# Chroma-Color_Rails.net
KiCad netlist of a schematic drawn in EAGLE
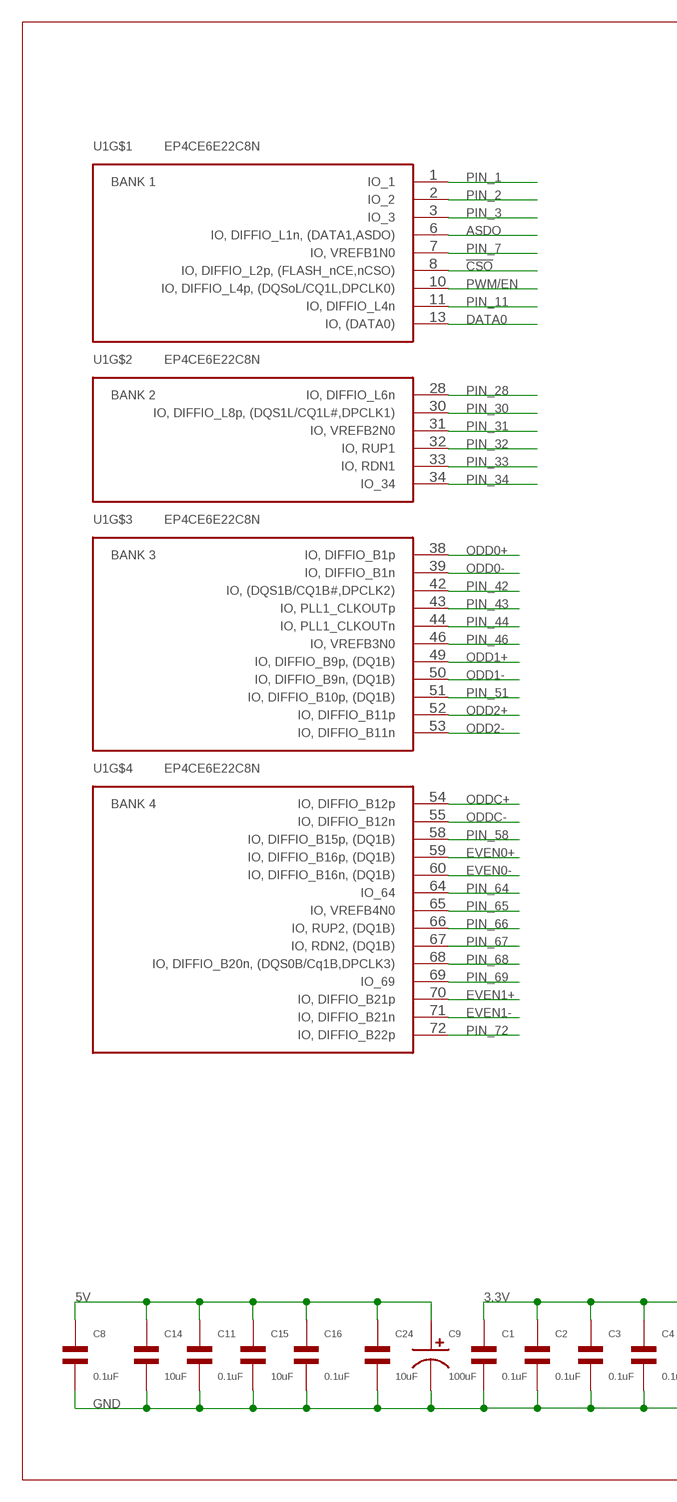
[diagram p0: schematic, sheet 1, part 1 of 2]
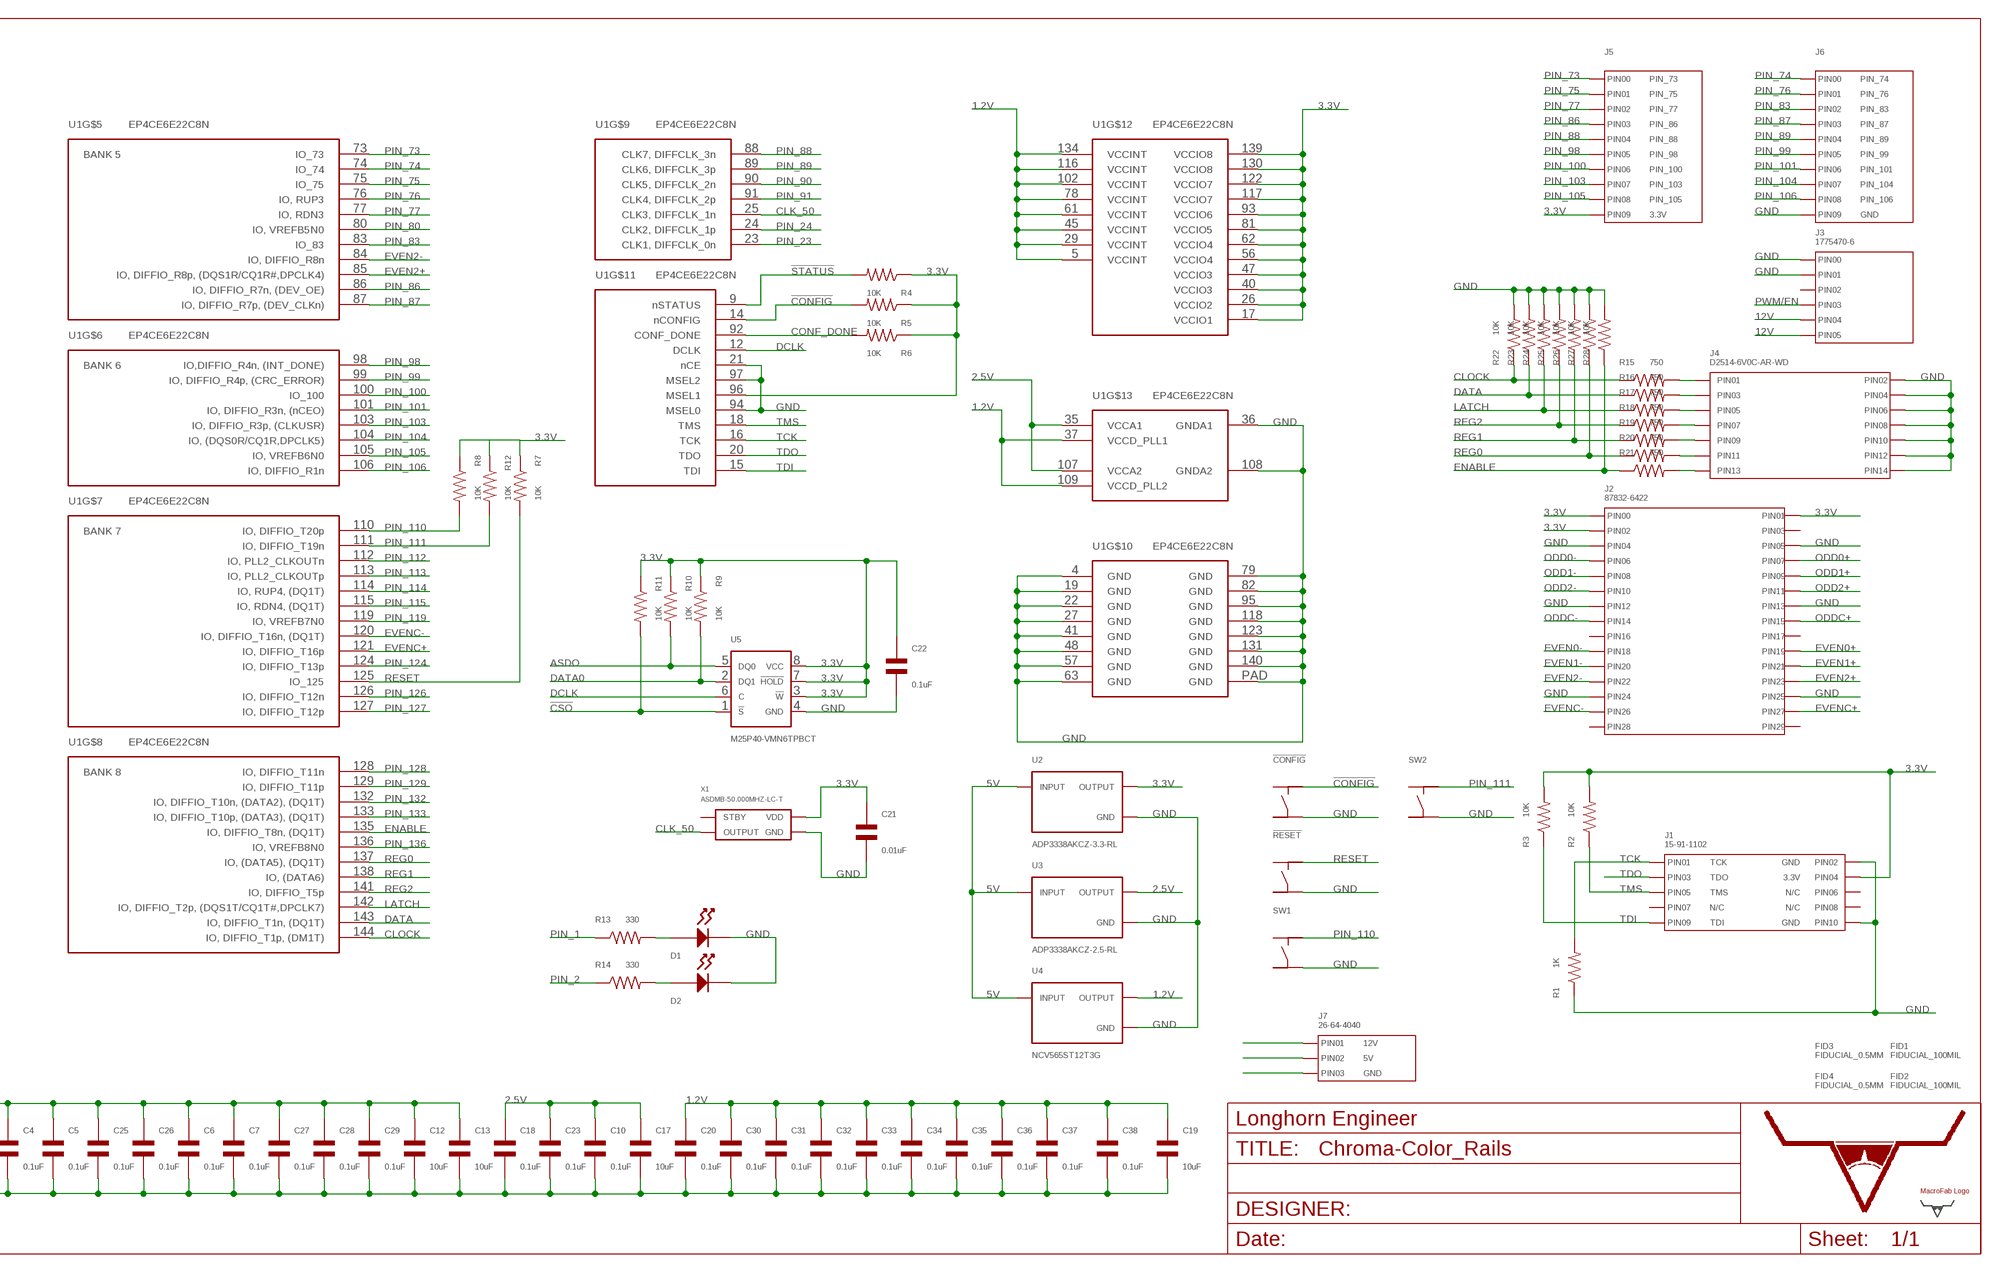
[diagram p1: schematic, sheet 1, part 2 of 2]

(export (version "E")
  (design (tool "Eeschema 10.0.6"))
  (components
    (comp (ref "!CONFIG")
      (value "TACT_4.2MM")
      (footprint "eagle-import:TACT4.2MM")
      (libsource (lib "eagle-import") (part "TACT_4.2MM"))
    )
    (comp (ref "!RESET")
      (value "TACT_4.2MM")
      (footprint "eagle-import:TACT4.2MM")
      (libsource (lib "eagle-import") (part "TACT_4.2MM"))
    )
    (comp (ref "C1")
      (value "0.1uF")
      (footprint "eagle-import:C0603")
      (libsource (lib "eagle-import") (part "CAPACITOR_NP_0603"))
    )
    (comp (ref "C2")
      (value "0.1uF")
      (footprint "eagle-import:C0603")
      (libsource (lib "eagle-import") (part "CAPACITOR_NP_0603"))
    )
    (comp (ref "C3")
      (value "0.1uF")
      (footprint "eagle-import:C0603")
      (libsource (lib "eagle-import") (part "CAPACITOR_NP_0603"))
    )
    (comp (ref "C4")
      (value "0.1uF")
      (footprint "eagle-import:C0603")
      (libsource (lib "eagle-import") (part "CAPACITOR_NP_0603"))
    )
    (comp (ref "C5")
      (value "0.1uF")
      (footprint "eagle-import:C0603")
      (libsource (lib "eagle-import") (part "CAPACITOR_NP_0603"))
    )
    (comp (ref "C6")
      (value "0.1uF")
      (footprint "eagle-import:C0603")
      (libsource (lib "eagle-import") (part "CAPACITOR_NP_0603"))
    )
    (comp (ref "C7")
      (value "0.1uF")
      (footprint "eagle-import:C0603")
      (libsource (lib "eagle-import") (part "CAPACITOR_NP_0603"))
    )
    (comp (ref "C8")
      (value "0.1uF")
      (footprint "eagle-import:C0603")
      (libsource (lib "eagle-import") (part "CAPACITOR_NP_0603"))
    )
    (comp (ref "C9")
      (value "100uF")
      (footprint "eagle-import:CP6.3MM")
      (libsource (lib "eagle-import") (part "CAPACITOR_P_6.3MM"))
    )
    (comp (ref "C10")
      (value "0.1uF")
      (footprint "eagle-import:C0603")
      (libsource (lib "eagle-import") (part "CAPACITOR_NP_0603"))
    )
    (comp (ref "C11")
      (value "0.1uF")
      (footprint "eagle-import:C0603")
      (libsource (lib "eagle-import") (part "CAPACITOR_NP_0603"))
    )
    (comp (ref "C12")
      (value "10uF")
      (footprint "eagle-import:C0603")
      (libsource (lib "eagle-import") (part "CAPACITOR_NP_0603"))
    )
    (comp (ref "C13")
      (value "10uF")
      (footprint "eagle-import:C0603")
      (libsource (lib "eagle-import") (part "CAPACITOR_NP_0603"))
    )
    (comp (ref "C14")
      (value "10uF")
      (footprint "eagle-import:C0603")
      (libsource (lib "eagle-import") (part "CAPACITOR_NP_0603"))
    )
    (comp (ref "C15")
      (value "10uF")
      (footprint "eagle-import:C0603")
      (libsource (lib "eagle-import") (part "CAPACITOR_NP_0603"))
    )
    (comp (ref "C16")
      (value "0.1uF")
      (footprint "eagle-import:C0603")
      (libsource (lib "eagle-import") (part "CAPACITOR_NP_0603"))
    )
    (comp (ref "C17")
      (value "10uF")
      (footprint "eagle-import:C0603")
      (libsource (lib "eagle-import") (part "CAPACITOR_NP_0603"))
    )
    (comp (ref "C18")
      (value "0.1uF")
      (footprint "eagle-import:C0603")
      (libsource (lib "eagle-import") (part "CAPACITOR_NP_0603"))
    )
    (comp (ref "C19")
      (value "10uF")
      (footprint "eagle-import:C0603")
      (libsource (lib "eagle-import") (part "CAPACITOR_NP_0603"))
    )
    (comp (ref "C20")
      (value "0.1uF")
      (footprint "eagle-import:C0603")
      (libsource (lib "eagle-import") (part "CAPACITOR_NP_0603"))
    )
    (comp (ref "C21")
      (value "0.01uF")
      (footprint "eagle-import:C0603")
      (libsource (lib "eagle-import") (part "CAPACITOR_NP_0603"))
    )
    (comp (ref "C22")
      (value "0.1uF")
      (footprint "eagle-import:C0603")
      (libsource (lib "eagle-import") (part "CAPACITOR_NP_0603"))
    )
    (comp (ref "C23")
      (value "0.1uF")
      (footprint "eagle-import:C0603")
      (libsource (lib "eagle-import") (part "CAPACITOR_NP_0603"))
    )
    (comp (ref "C24")
      (value "10uF")
      (footprint "eagle-import:C0603")
      (libsource (lib "eagle-import") (part "CAPACITOR_NP_0603"))
    )
    (comp (ref "C25")
      (value "0.1uF")
      (footprint "eagle-import:C0603")
      (libsource (lib "eagle-import") (part "CAPACITOR_NP_0603"))
    )
    (comp (ref "C26")
      (value "0.1uF")
      (footprint "eagle-import:C0603")
      (libsource (lib "eagle-import") (part "CAPACITOR_NP_0603"))
    )
    (comp (ref "C27")
      (value "0.1uF")
      (footprint "eagle-import:C0603")
      (libsource (lib "eagle-import") (part "CAPACITOR_NP_0603"))
    )
    (comp (ref "C28")
      (value "0.1uF")
      (footprint "eagle-import:C0603")
      (libsource (lib "eagle-import") (part "CAPACITOR_NP_0603"))
    )
    (comp (ref "C29")
      (value "0.1uF")
      (footprint "eagle-import:C0603")
      (libsource (lib "eagle-import") (part "CAPACITOR_NP_0603"))
    )
    (comp (ref "C30")
      (value "0.1uF")
      (footprint "eagle-import:C0603")
      (libsource (lib "eagle-import") (part "CAPACITOR_NP_0603"))
    )
    (comp (ref "C31")
      (value "0.1uF")
      (footprint "eagle-import:C0603")
      (libsource (lib "eagle-import") (part "CAPACITOR_NP_0603"))
    )
    (comp (ref "C32")
      (value "0.1uF")
      (footprint "eagle-import:C0603")
      (libsource (lib "eagle-import") (part "CAPACITOR_NP_0603"))
    )
    (comp (ref "C33")
      (value "0.1uF")
      (footprint "eagle-import:C0603")
      (libsource (lib "eagle-import") (part "CAPACITOR_NP_0603"))
    )
    (comp (ref "C34")
      (value "0.1uF")
      (footprint "eagle-import:C0603")
      (libsource (lib "eagle-import") (part "CAPACITOR_NP_0603"))
    )
    (comp (ref "C35")
      (value "0.1uF")
      (footprint "eagle-import:C0603")
      (libsource (lib "eagle-import") (part "CAPACITOR_NP_0603"))
    )
    (comp (ref "C36")
      (value "0.1uF")
      (footprint "eagle-import:C0603")
      (libsource (lib "eagle-import") (part "CAPACITOR_NP_0603"))
    )
    (comp (ref "C37")
      (value "0.1uF")
      (footprint "eagle-import:C0603")
      (libsource (lib "eagle-import") (part "CAPACITOR_NP_0603"))
    )
    (comp (ref "C38")
      (value "0.1uF")
      (footprint "eagle-import:C0603")
      (libsource (lib "eagle-import") (part "CAPACITOR_NP_0603"))
    )
    (comp (ref "D1")
      (value "LED_SINGLE_0805")
      (footprint "eagle-import:LED0805")
      (libsource (lib "eagle-import") (part "LED_SINGLE_0805"))
    )
    (comp (ref "D2")
      (value "LED_SINGLE_0805")
      (footprint "eagle-import:LED0805")
      (libsource (lib "eagle-import") (part "LED_SINGLE_0805"))
    )
    (comp (ref "FID1")
      (value "FIDUCIAL_100MIL")
      (footprint "eagle-import:FIDUCIAL_100MIL")
      (libsource (lib "eagle-import") (part "FIDUCIAL_100MIL"))
    )
    (comp (ref "FID2")
      (value "FIDUCIAL_100MIL")
      (footprint "eagle-import:FIDUCIAL_100MIL")
      (libsource (lib "eagle-import") (part "FIDUCIAL_100MIL"))
    )
    (comp (ref "FID3")
      (value "FIDUCIAL_0.5MM")
      (footprint "eagle-import:FIDUCIAL_0.5MM")
      (libsource (lib "eagle-import") (part "FIDUCIAL_0.5MM"))
    )
    (comp (ref "FID4")
      (value "FIDUCIAL_0.5MM")
      (footprint "eagle-import:FIDUCIAL_0.5MM")
      (libsource (lib "eagle-import") (part "FIDUCIAL_0.5MM"))
    )
    (comp (ref "J1")
      (value "15-91-1102")
      (footprint "eagle-import:15-91-1102")
      (fields
        (field (name "LABEL01") "TCK")
        (field (name "LABEL02") "GND")
        (field (name "LABEL03") "TDO")
        (field (name "LABEL04") "3.3V")
        (field (name "LABEL05") "TMS")
        (field (name "LABEL06") "N/C")
        (field (name "LABEL07") "N/C")
        (field (name "LABEL08") "N/C")
        (field (name "LABEL09") "TDI")
        (field (name "LABEL10") "GND")
      )
      (libsource (lib "eagle-import") (part "15-91-1102"))
    )
    (comp (ref "J2")
      (value "87832-6422")
      (footprint "eagle-import:87832-6422")
      (libsource (lib "eagle-import") (part "87832-6422"))
    )
    (comp (ref "J3")
      (value "1775470-6")
      (footprint "eagle-import:1775470-6")
      (libsource (lib "eagle-import") (part "1775470-6"))
    )
    (comp (ref "J4")
      (value "D2514-6V0C-AR-WD")
      (footprint "eagle-import:D2514-6V0C-AR-WD")
      (libsource (lib "eagle-import") (part "SMT_02X07D2514-6V0C-AR-WD"))
    )
    (comp (ref "J5")
      (value "HEADER_01X10_PTH_2.54MM")
      (footprint "eagle-import:PTH_2.54MM_01X10")
      (fields
        (field (name "LABEL00") "PIN_73")
        (field (name "LABEL01") "PIN_75")
        (field (name "LABEL02") "PIN_77")
        (field (name "LABEL03") "PIN_86")
        (field (name "LABEL04") "PIN_88")
        (field (name "LABEL05") "PIN_98")
        (field (name "LABEL06") "PIN_100")
        (field (name "LABEL07") "PIN_103")
        (field (name "LABEL08") "PIN_105")
        (field (name "LABEL09") "3.3V")
      )
      (libsource (lib "eagle-import") (part "HEADER_01X10_PTH_2.54MM"))
    )
    (comp (ref "J6")
      (value "HEADER_01X10_PTH_2.54MM")
      (footprint "eagle-import:PTH_2.54MM_01X10")
      (fields
        (field (name "LABEL00") "PIN_74")
        (field (name "LABEL01") "PIN_76")
        (field (name "LABEL02") "PIN_83")
        (field (name "LABEL03") "PIN_87")
        (field (name "LABEL04") "PIN_89")
        (field (name "LABEL05") "PIN_99")
        (field (name "LABEL06") "PIN_101")
        (field (name "LABEL07") "PIN_104")
        (field (name "LABEL08") "PIN_106")
        (field (name "LABEL09") "GND")
      )
      (libsource (lib "eagle-import") (part "HEADER_01X10_PTH_2.54MM"))
    )
    (comp (ref "J7")
      (value "26-64-4040")
      (footprint "eagle-import:MOLEX_KK_4_P1")
      (fields (field (name "LABEL01") "12V") (field (name "LABEL02") "5V") (field (name "LABEL03") "GND"))
      (libsource (lib "eagle-import") (part "HEADER_01X03MOLEX_KK_4_P1"))
    )
    (comp (ref "R1")
      (value "1K")
      (footprint "eagle-import:R0603")
      (libsource (lib "eagle-import") (part "RESISTOR_0603"))
    )
    (comp (ref "R2")
      (value "10K")
      (footprint "eagle-import:R0603")
      (libsource (lib "eagle-import") (part "RESISTOR_0603"))
    )
    (comp (ref "R3")
      (value "10K")
      (footprint "eagle-import:R0603")
      (libsource (lib "eagle-import") (part "RESISTOR_0603"))
    )
    (comp (ref "R4")
      (value "10K")
      (footprint "eagle-import:R0603")
      (libsource (lib "eagle-import") (part "RESISTOR_0603"))
    )
    (comp (ref "R5")
      (value "10K")
      (footprint "eagle-import:R0603")
      (libsource (lib "eagle-import") (part "RESISTOR_0603"))
    )
    (comp (ref "R6")
      (value "10K")
      (footprint "eagle-import:R0603")
      (libsource (lib "eagle-import") (part "RESISTOR_0603"))
    )
    (comp (ref "R7")
      (value "10K")
      (footprint "eagle-import:R0603")
      (libsource (lib "eagle-import") (part "RESISTOR_0603"))
    )
    (comp (ref "R8")
      (value "10K")
      (footprint "eagle-import:R0603")
      (libsource (lib "eagle-import") (part "RESISTOR_0603"))
    )
    (comp (ref "R9")
      (value "10K")
      (footprint "eagle-import:R0603")
      (libsource (lib "eagle-import") (part "RESISTOR_0603"))
    )
    (comp (ref "R10")
      (value "10K")
      (footprint "eagle-import:R0603")
      (libsource (lib "eagle-import") (part "RESISTOR_0603"))
    )
    (comp (ref "R11")
      (value "10K")
      (footprint "eagle-import:R0603")
      (libsource (lib "eagle-import") (part "RESISTOR_0603"))
    )
    (comp (ref "R12")
      (value "10K")
      (footprint "eagle-import:R0603")
      (libsource (lib "eagle-import") (part "RESISTOR_0603"))
    )
    (comp (ref "R13")
      (value "330")
      (footprint "eagle-import:R0603")
      (libsource (lib "eagle-import") (part "RESISTOR_0603"))
    )
    (comp (ref "R14")
      (value "330")
      (footprint "eagle-import:R0603")
      (libsource (lib "eagle-import") (part "RESISTOR_0603"))
    )
    (comp (ref "R15")
      (value "750")
      (footprint "eagle-import:R0603")
      (libsource (lib "eagle-import") (part "RESISTOR_0603"))
    )
    (comp (ref "R16")
      (value "750")
      (footprint "eagle-import:R0603")
      (libsource (lib "eagle-import") (part "RESISTOR_0603"))
    )
    (comp (ref "R17")
      (value "750")
      (footprint "eagle-import:R0603")
      (libsource (lib "eagle-import") (part "RESISTOR_0603"))
    )
    (comp (ref "R18")
      (value "750")
      (footprint "eagle-import:R0603")
      (libsource (lib "eagle-import") (part "RESISTOR_0603"))
    )
    (comp (ref "R19")
      (value "750")
      (footprint "eagle-import:R0603")
      (libsource (lib "eagle-import") (part "RESISTOR_0603"))
    )
    (comp (ref "R20")
      (value "750")
      (footprint "eagle-import:R0603")
      (libsource (lib "eagle-import") (part "RESISTOR_0603"))
    )
    (comp (ref "R21")
      (value "750")
      (footprint "eagle-import:R0603")
      (libsource (lib "eagle-import") (part "RESISTOR_0603"))
    )
    (comp (ref "R22")
      (value "10K")
      (footprint "eagle-import:R0603")
      (libsource (lib "eagle-import") (part "RESISTOR_0603"))
    )
    (comp (ref "R23")
      (value "10K")
      (footprint "eagle-import:R0603")
      (libsource (lib "eagle-import") (part "RESISTOR_0603"))
    )
    (comp (ref "R24")
      (value "10K")
      (footprint "eagle-import:R0603")
      (libsource (lib "eagle-import") (part "RESISTOR_0603"))
    )
    (comp (ref "R25")
      (value "10K")
      (footprint "eagle-import:R0603")
      (libsource (lib "eagle-import") (part "RESISTOR_0603"))
    )
    (comp (ref "R26")
      (value "10K")
      (footprint "eagle-import:R0603")
      (libsource (lib "eagle-import") (part "RESISTOR_0603"))
    )
    (comp (ref "R27")
      (value "10K")
      (footprint "eagle-import:R0603")
      (libsource (lib "eagle-import") (part "RESISTOR_0603"))
    )
    (comp (ref "R28")
      (value "10K")
      (footprint "eagle-import:R0603")
      (libsource (lib "eagle-import") (part "RESISTOR_0603"))
    )
    (comp (ref "SW1")
      (value "TACT_4.2MM")
      (footprint "eagle-import:TACT4.2MM")
      (libsource (lib "eagle-import") (part "TACT_4.2MM"))
    )
    (comp (ref "SW2")
      (value "TACT_4.2MM")
      (footprint "eagle-import:TACT4.2MM")
      (libsource (lib "eagle-import") (part "TACT_4.2MM"))
    )
    (comp (ref "U$1")
      (value "LHE_FRAME")
      (footprint "eagle-import:LHE_FRAME")
      (fields (field (name "DNAME") "Parker Dillmann") (field (name "REVNUM") "REV: 2"))
      (libsource (lib "eagle-import") (part "LHE_FRAME"))
    )
    (comp (ref "U$2")
      (value "MF_LOGOLOGO_MEDIUM")
      (footprint "eagle-import:MF_LOGO_MEDIUM")
      (libsource (lib "eagle-import") (part "MF_LOGOLOGO_MEDIUM"))
    )
    (comp (ref "U$3")
      (value "LHE_LOGOLHE_LOGO")
      (footprint "eagle-import:LHE_LOGO")
      (libsource (lib "eagle-import") (part "LHE_LOGOLHE_LOGO"))
    )
    (comp (ref "U1")
      (value "EP4CE6E22C8N")
      (footprint "eagle-import:EQFP-144")
      (libsource (lib "eagle-import") (part "EP4CE6E22C8N"))
    )
    (comp (ref "U2")
      (value "ADP3338AKCZ-3.3-RL")
      (footprint "eagle-import:SOT-223B")
      (libsource (lib "eagle-import") (part "ADP3338AKCZ-3.3-RL"))
    )
    (comp (ref "U3")
      (value "ADP3338AKCZ-2.5-RL")
      (footprint "eagle-import:SOT-223B")
      (libsource (lib "eagle-import") (part "ADP3338AKCZ-2.5-RL"))
    )
    (comp (ref "U4")
      (value "NCV565ST12T3G")
      (footprint "eagle-import:SOT-223B")
      (libsource (lib "eagle-import") (part "NCV565ST12T3G"))
    )
    (comp (ref "U5")
      (value "M25P40-VMN6TPBCT")
      (footprint "eagle-import:SOIC-8")
      (libsource (lib "eagle-import") (part "M25P40-VMN6TPBCT"))
    )
    (comp (ref "X1")
      (value "ASDMB-50.000MHZ-LC-T")
      (footprint "eagle-import:ASDMB")
      (libsource (lib "eagle-import") (part "ASDMB"))
    )
  )
  (nets
    (net (code "1") (name "/1.2V") (class "Default")
      (node (ref "C19") (pin "P$1") (pinfunction "P$1_P$1") (pintype "passive"))
      (node (ref "C20") (pin "P$1") (pinfunction "P$1_P$1") (pintype "passive"))
      (node (ref "C30") (pin "P$1") (pinfunction "P$1_P$1") (pintype "passive"))
      (node (ref "C31") (pin "P$1") (pinfunction "P$1_P$1") (pintype "passive"))
      (node (ref "C32") (pin "P$1") (pinfunction "P$1_P$1") (pintype "passive"))
      (node (ref "C33") (pin "P$1") (pinfunction "P$1_P$1") (pintype "passive"))
      (node (ref "C34") (pin "P$1") (pinfunction "P$1_P$1") (pintype "passive"))
      (node (ref "C35") (pin "P$1") (pinfunction "P$1_P$1") (pintype "passive"))
      (node (ref "C36") (pin "P$1") (pinfunction "P$1_P$1") (pintype "passive"))
      (node (ref "C37") (pin "P$1") (pinfunction "P$1_P$1") (pintype "passive"))
      (node (ref "C38") (pin "P$1") (pinfunction "P$1_P$1") (pintype "passive"))
      (node (ref "U1") (pin "102") (pinfunction "102_102") (pintype "bidirectional"))
      (node (ref "U1") (pin "109") (pinfunction "109_109") (pintype "bidirectional"))
      (node (ref "U1") (pin "116") (pinfunction "116_116") (pintype "bidirectional"))
      (node (ref "U1") (pin "134") (pinfunction "134_134") (pintype "bidirectional"))
      (node (ref "U1") (pin "29") (pinfunction "29_29") (pintype "bidirectional"))
      (node (ref "U1") (pin "37") (pinfunction "37_37") (pintype "bidirectional"))
      (node (ref "U1") (pin "45") (pinfunction "45_45") (pintype "bidirectional"))
      (node (ref "U1") (pin "5") (pinfunction "5_5") (pintype "bidirectional"))
      (node (ref "U1") (pin "61") (pinfunction "61_61") (pintype "bidirectional"))
      (node (ref "U1") (pin "78") (pinfunction "78_78") (pintype "bidirectional"))
      (node (ref "U4") (pin "2") (pinfunction "OUT_2") (pintype "bidirectional"))
      (node (ref "U4") (pin "PAD") (pinfunction "OUT_PAD") (pintype "bidirectional"))
    )
    (net (code "2") (name "/2.5V") (class "Default")
      (node (ref "C10") (pin "P$1") (pinfunction "P$1_P$1") (pintype "passive"))
      (node (ref "C17") (pin "P$1") (pinfunction "P$1_P$1") (pintype "passive"))
      (node (ref "C18") (pin "P$1") (pinfunction "P$1_P$1") (pintype "passive"))
      (node (ref "C23") (pin "P$1") (pinfunction "P$1_P$1") (pintype "passive"))
      (node (ref "U1") (pin "107") (pinfunction "107_107") (pintype "bidirectional"))
      (node (ref "U1") (pin "35") (pinfunction "35_35") (pintype "bidirectional"))
      (node (ref "U3") (pin "2") (pinfunction "OUT_2") (pintype "bidirectional"))
      (node (ref "U3") (pin "PAD") (pinfunction "OUT_PAD") (pintype "bidirectional"))
    )
    (net (code "3") (name "/3.3V") (class "Default")
      (node (ref "C1") (pin "P$1") (pinfunction "P$1_P$1") (pintype "passive"))
      (node (ref "C12") (pin "P$1") (pinfunction "P$1_P$1") (pintype "passive"))
      (node (ref "C13") (pin "P$1") (pinfunction "P$1_P$1") (pintype "passive"))
      (node (ref "C2") (pin "P$1") (pinfunction "P$1_P$1") (pintype "passive"))
      (node (ref "C21") (pin "P$1") (pinfunction "P$1_P$1") (pintype "passive"))
      (node (ref "C22") (pin "P$1") (pinfunction "P$1_P$1") (pintype "passive"))
      (node (ref "C25") (pin "P$1") (pinfunction "P$1_P$1") (pintype "passive"))
      (node (ref "C26") (pin "P$1") (pinfunction "P$1_P$1") (pintype "passive"))
      (node (ref "C27") (pin "P$1") (pinfunction "P$1_P$1") (pintype "passive"))
      (node (ref "C28") (pin "P$1") (pinfunction "P$1_P$1") (pintype "passive"))
      (node (ref "C29") (pin "P$1") (pinfunction "P$1_P$1") (pintype "passive"))
      (node (ref "C3") (pin "P$1") (pinfunction "P$1_P$1") (pintype "passive"))
      (node (ref "C4") (pin "P$1") (pinfunction "P$1_P$1") (pintype "passive"))
      (node (ref "C5") (pin "P$1") (pinfunction "P$1_P$1") (pintype "passive"))
      (node (ref "C6") (pin "P$1") (pinfunction "P$1_P$1") (pintype "passive"))
      (node (ref "C7") (pin "P$1") (pinfunction "P$1_P$1") (pintype "passive"))
      (node (ref "J1") (pin "4") (pinfunction "PIN4_4") (pintype "bidirectional"))
      (node (ref "J2") (pin "P$1") (pinfunction "PIN0_P$1") (pintype "bidirectional"))
      (node (ref "J2") (pin "P$2") (pinfunction "PIN1_P$2") (pintype "bidirectional"))
      (node (ref "J2") (pin "P$3") (pinfunction "PIN2_P$3") (pintype "bidirectional"))
      (node (ref "J5") (pin "P$10") (pinfunction "PIN9_P$10") (pintype "bidirectional"))
      (node (ref "R10") (pin "P$1") (pinfunction "P$1_P$1") (pintype "passive"))
      (node (ref "R11") (pin "P$1") (pinfunction "P$1_P$1") (pintype "passive"))
      (node (ref "R12") (pin "P$1") (pinfunction "P$1_P$1") (pintype "passive"))
      (node (ref "R2") (pin "P$2") (pinfunction "P$2_P$2") (pintype "passive"))
      (node (ref "R3") (pin "P$2") (pinfunction "P$2_P$2") (pintype "passive"))
      (node (ref "R4") (pin "P$1") (pinfunction "P$1_P$1") (pintype "passive"))
      (node (ref "R5") (pin "P$1") (pinfunction "P$1_P$1") (pintype "passive"))
      (node (ref "R6") (pin "P$1") (pinfunction "P$1_P$1") (pintype "passive"))
      (node (ref "R7") (pin "P$1") (pinfunction "P$1_P$1") (pintype "passive"))
      (node (ref "R8") (pin "P$1") (pinfunction "P$1_P$1") (pintype "passive"))
      (node (ref "R9") (pin "P$1") (pinfunction "P$1_P$1") (pintype "passive"))
      (node (ref "U1") (pin "117") (pinfunction "117_117") (pintype "bidirectional"))
      (node (ref "U1") (pin "122") (pinfunction "122_122") (pintype "bidirectional"))
      (node (ref "U1") (pin "130") (pinfunction "130_130") (pintype "bidirectional"))
      (node (ref "U1") (pin "139") (pinfunction "139_139") (pintype "bidirectional"))
      (node (ref "U1") (pin "17") (pinfunction "17_17") (pintype "bidirectional"))
      (node (ref "U1") (pin "26") (pinfunction "26_26") (pintype "bidirectional"))
      (node (ref "U1") (pin "40") (pinfunction "40_40") (pintype "bidirectional"))
      (node (ref "U1") (pin "47") (pinfunction "47_47") (pintype "bidirectional"))
      (node (ref "U1") (pin "56") (pinfunction "56_56") (pintype "bidirectional"))
      (node (ref "U1") (pin "62") (pinfunction "62_62") (pintype "bidirectional"))
      (node (ref "U1") (pin "81") (pinfunction "81_81") (pintype "bidirectional"))
      (node (ref "U1") (pin "93") (pinfunction "93_93") (pintype "bidirectional"))
      (node (ref "U1") (pin "96") (pinfunction "96_96") (pintype "bidirectional"))
      (node (ref "U2") (pin "2") (pinfunction "OUT_2") (pintype "bidirectional"))
      (node (ref "U2") (pin "PAD") (pinfunction "OUT_PAD") (pintype "bidirectional"))
      (node (ref "U5") (pin "3") (pinfunction "~{W}_3") (pintype "bidirectional"))
      (node (ref "U5") (pin "7") (pinfunction "~{HOLD}_7") (pintype "bidirectional"))
      (node (ref "U5") (pin "8") (pinfunction "VCC_8") (pintype "bidirectional"))
      (node (ref "X1") (pin "P$4") (pinfunction "VDD_P$4") (pintype "bidirectional"))
    )
    (net (code "4") (name "/5V") (class "Default")
      (node (ref "C11") (pin "P$1") (pinfunction "P$1_P$1") (pintype "passive"))
      (node (ref "C14") (pin "P$1") (pinfunction "P$1_P$1") (pintype "passive"))
      (node (ref "C15") (pin "P$1") (pinfunction "P$1_P$1") (pintype "passive"))
      (node (ref "C16") (pin "P$1") (pinfunction "P$1_P$1") (pintype "passive"))
      (node (ref "C24") (pin "P$1") (pinfunction "P$1_P$1") (pintype "passive"))
      (node (ref "C8") (pin "P$1") (pinfunction "P$1_P$1") (pintype "passive"))
      (node (ref "C9") (pin "P$1") (pinfunction "P$1_P$1") (pintype "passive"))
      (node (ref "J7") (pin "3") (pinfunction "PIN2_3") (pintype "bidirectional"))
      (node (ref "U2") (pin "3") (pinfunction "IN_3") (pintype "bidirectional"))
      (node (ref "U3") (pin "3") (pinfunction "IN_3") (pintype "bidirectional"))
      (node (ref "U4") (pin "3") (pinfunction "IN_3") (pintype "bidirectional"))
    )
    (net (code "5") (name "/12V") (class "Default")
      (node (ref "J3") (pin "P$5") (pinfunction "PIN4_P$5") (pintype "bidirectional"))
      (node (ref "J3") (pin "P$6") (pinfunction "PIN5_P$6") (pintype "bidirectional"))
      (node (ref "J7") (pin "2") (pinfunction "PIN1_2") (pintype "bidirectional"))
    )
    (net (code "6") (name "/ASDO") (class "Default")
      (node (ref "R10") (pin "P$2") (pinfunction "P$2_P$2") (pintype "passive"))
      (node (ref "U1") (pin "6") (pinfunction "6_6") (pintype "bidirectional"))
      (node (ref "U5") (pin "5") (pinfunction "DQ0_5") (pintype "bidirectional"))
    )
    (net (code "7") (name "/CLK_50") (class "Default")
      (node (ref "U1") (pin "25") (pinfunction "25_25") (pintype "bidirectional"))
      (node (ref "X1") (pin "P$3") (pinfunction "OUTPUT_P$3") (pintype "bidirectional"))
    )
    (net (code "8") (name "/CLOCK") (class "Default")
      (node (ref "R15") (pin "P$1") (pinfunction "P$1_P$1") (pintype "passive"))
      (node (ref "R22") (pin "P$1") (pinfunction "P$1_P$1") (pintype "passive"))
      (node (ref "U1") (pin "144") (pinfunction "144_144") (pintype "bidirectional"))
    )
    (net (code "9") (name "/CONF_DONE") (class "Default")
      (node (ref "R6") (pin "P$2") (pinfunction "P$2_P$2") (pintype "passive"))
      (node (ref "U1") (pin "92") (pinfunction "92_92") (pintype "bidirectional"))
    )
    (net (code "10") (name "/DATA") (class "Default")
      (node (ref "R16") (pin "P$1") (pinfunction "P$1_P$1") (pintype "passive"))
      (node (ref "R23") (pin "P$1") (pinfunction "P$1_P$1") (pintype "passive"))
      (node (ref "U1") (pin "143") (pinfunction "143_143") (pintype "bidirectional"))
    )
    (net (code "11") (name "/DATA0") (class "Default")
      (node (ref "R9") (pin "P$2") (pinfunction "P$2_P$2") (pintype "passive"))
      (node (ref "U1") (pin "13") (pinfunction "13_13") (pintype "bidirectional"))
      (node (ref "U5") (pin "2") (pinfunction "DQ1_2") (pintype "bidirectional"))
    )
    (net (code "12") (name "/DCLK") (class "Default")
      (node (ref "U1") (pin "12") (pinfunction "12_12") (pintype "bidirectional"))
      (node (ref "U5") (pin "6") (pinfunction "C_6") (pintype "bidirectional"))
    )
    (net (code "13") (name "/ENABLE") (class "Default")
      (node (ref "R21") (pin "P$1") (pinfunction "P$1_P$1") (pintype "passive"))
      (node (ref "R28") (pin "P$1") (pinfunction "P$1_P$1") (pintype "passive"))
      (node (ref "U1") (pin "135") (pinfunction "135_135") (pintype "bidirectional"))
    )
    (net (code "14") (name "/EVEN0+") (class "Default")
      (node (ref "J2") (pin "P$20") (pinfunction "PIN19_P$20") (pintype "bidirectional"))
      (node (ref "U1") (pin "59") (pinfunction "59_59") (pintype "bidirectional"))
    )
    (net (code "15") (name "/EVEN0-") (class "Default")
      (node (ref "J2") (pin "P$19") (pinfunction "PIN18_P$19") (pintype "bidirectional"))
      (node (ref "U1") (pin "60") (pinfunction "60_60") (pintype "bidirectional"))
    )
    (net (code "16") (name "/EVEN1+") (class "Default")
      (node (ref "J2") (pin "P$22") (pinfunction "PIN21_P$22") (pintype "bidirectional"))
      (node (ref "U1") (pin "70") (pinfunction "70_70") (pintype "bidirectional"))
    )
    (net (code "17") (name "/EVEN1-") (class "Default")
      (node (ref "J2") (pin "P$21") (pinfunction "PIN20_P$21") (pintype "bidirectional"))
      (node (ref "U1") (pin "71") (pinfunction "71_71") (pintype "bidirectional"))
    )
    (net (code "18") (name "/EVEN2+") (class "Default")
      (node (ref "J2") (pin "P$24") (pinfunction "PIN23_P$24") (pintype "bidirectional"))
      (node (ref "U1") (pin "85") (pinfunction "85_85") (pintype "bidirectional"))
    )
    (net (code "19") (name "/EVEN2-") (class "Default")
      (node (ref "J2") (pin "P$23") (pinfunction "PIN22_P$23") (pintype "bidirectional"))
      (node (ref "U1") (pin "84") (pinfunction "84_84") (pintype "bidirectional"))
    )
    (net (code "20") (name "/EVENC+") (class "Default")
      (node (ref "J2") (pin "P$28") (pinfunction "PIN27_P$28") (pintype "bidirectional"))
      (node (ref "U1") (pin "121") (pinfunction "121_121") (pintype "bidirectional"))
    )
    (net (code "21") (name "/EVENC-") (class "Default")
      (node (ref "J2") (pin "P$27") (pinfunction "PIN26_P$27") (pintype "bidirectional"))
      (node (ref "U1") (pin "120") (pinfunction "120_120") (pintype "bidirectional"))
    )
    (net (code "22") (name "/GND") (class "Default")
      (node (ref "!CONFIG") (pin "P$4") (pinfunction "P$4_P$4") (pintype "bidirectional"))
      (node (ref "!RESET") (pin "P$4") (pinfunction "P$4_P$4") (pintype "bidirectional"))
      (node (ref "C1") (pin "P$2") (pinfunction "P$2_P$2") (pintype "passive"))
      (node (ref "C10") (pin "P$2") (pinfunction "P$2_P$2") (pintype "passive"))
      (node (ref "C11") (pin "P$2") (pinfunction "P$2_P$2") (pintype "passive"))
      (node (ref "C12") (pin "P$2") (pinfunction "P$2_P$2") (pintype "passive"))
      (node (ref "C13") (pin "P$2") (pinfunction "P$2_P$2") (pintype "passive"))
      (node (ref "C14") (pin "P$2") (pinfunction "P$2_P$2") (pintype "passive"))
      (node (ref "C15") (pin "P$2") (pinfunction "P$2_P$2") (pintype "passive"))
      (node (ref "C16") (pin "P$2") (pinfunction "P$2_P$2") (pintype "passive"))
      (node (ref "C17") (pin "P$2") (pinfunction "P$2_P$2") (pintype "passive"))
      (node (ref "C18") (pin "P$2") (pinfunction "P$2_P$2") (pintype "passive"))
      (node (ref "C19") (pin "P$2") (pinfunction "P$2_P$2") (pintype "passive"))
      (node (ref "C2") (pin "P$2") (pinfunction "P$2_P$2") (pintype "passive"))
      (node (ref "C20") (pin "P$2") (pinfunction "P$2_P$2") (pintype "passive"))
      (node (ref "C21") (pin "P$2") (pinfunction "P$2_P$2") (pintype "passive"))
      (node (ref "C22") (pin "P$2") (pinfunction "P$2_P$2") (pintype "passive"))
      (node (ref "C23") (pin "P$2") (pinfunction "P$2_P$2") (pintype "passive"))
      (node (ref "C24") (pin "P$2") (pinfunction "P$2_P$2") (pintype "passive"))
      (node (ref "C25") (pin "P$2") (pinfunction "P$2_P$2") (pintype "passive"))
      (node (ref "C26") (pin "P$2") (pinfunction "P$2_P$2") (pintype "passive"))
      (node (ref "C27") (pin "P$2") (pinfunction "P$2_P$2") (pintype "passive"))
      (node (ref "C28") (pin "P$2") (pinfunction "P$2_P$2") (pintype "passive"))
      (node (ref "C29") (pin "P$2") (pinfunction "P$2_P$2") (pintype "passive"))
      (node (ref "C3") (pin "P$2") (pinfunction "P$2_P$2") (pintype "passive"))
      (node (ref "C30") (pin "P$2") (pinfunction "P$2_P$2") (pintype "passive"))
      (node (ref "C31") (pin "P$2") (pinfunction "P$2_P$2") (pintype "passive"))
      (node (ref "C32") (pin "P$2") (pinfunction "P$2_P$2") (pintype "passive"))
      (node (ref "C33") (pin "P$2") (pinfunction "P$2_P$2") (pintype "passive"))
      (node (ref "C34") (pin "P$2") (pinfunction "P$2_P$2") (pintype "passive"))
      (node (ref "C35") (pin "P$2") (pinfunction "P$2_P$2") (pintype "passive"))
      (node (ref "C36") (pin "P$2") (pinfunction "P$2_P$2") (pintype "passive"))
      (node (ref "C37") (pin "P$2") (pinfunction "P$2_P$2") (pintype "passive"))
      (node (ref "C38") (pin "P$2") (pinfunction "P$2_P$2") (pintype "passive"))
      (node (ref "C4") (pin "P$2") (pinfunction "P$2_P$2") (pintype "passive"))
      (node (ref "C5") (pin "P$2") (pinfunction "P$2_P$2") (pintype "passive"))
      (node (ref "C6") (pin "P$2") (pinfunction "P$2_P$2") (pintype "passive"))
      (node (ref "C7") (pin "P$2") (pinfunction "P$2_P$2") (pintype "passive"))
      (node (ref "C8") (pin "P$2") (pinfunction "P$2_P$2") (pintype "passive"))
      (node (ref "C9") (pin "P$2") (pinfunction "P$2_P$2") (pintype "passive"))
      (node (ref "D1") (pin "CATHODE") (pinfunction "CATHODE_CATHODE") (pintype "power_in"))
      (node (ref "D2") (pin "CATHODE") (pinfunction "CATHODE_CATHODE") (pintype "power_in"))
      (node (ref "J1") (pin "10") (pinfunction "PIN10_10") (pintype "bidirectional"))
      (node (ref "J1") (pin "2") (pinfunction "PIN2_2") (pintype "bidirectional"))
      (node (ref "J2") (pin "P$13") (pinfunction "PIN12_P$13") (pintype "bidirectional"))
      (node (ref "J2") (pin "P$14") (pinfunction "PIN13_P$14") (pintype "bidirectional"))
      (node (ref "J2") (pin "P$25") (pinfunction "PIN24_P$25") (pintype "bidirectional"))
      (node (ref "J2") (pin "P$26") (pinfunction "PIN25_P$26") (pintype "bidirectional"))
      (node (ref "J2") (pin "P$5") (pinfunction "PIN4_P$5") (pintype "bidirectional"))
      (node (ref "J2") (pin "P$6") (pinfunction "PIN5_P$6") (pintype "bidirectional"))
      (node (ref "J3") (pin "P$1") (pinfunction "PIN0_P$1") (pintype "bidirectional"))
      (node (ref "J3") (pin "P$2") (pinfunction "PIN1_P$2") (pintype "bidirectional"))
      (node (ref "J4") (pin "10") (pinfunction "PIN10_10") (pintype "bidirectional"))
      (node (ref "J4") (pin "12") (pinfunction "PIN12_12") (pintype "bidirectional"))
      (node (ref "J4") (pin "14") (pinfunction "PIN14_14") (pintype "bidirectional"))
      (node (ref "J4") (pin "2") (pinfunction "PIN2_2") (pintype "bidirectional"))
      (node (ref "J4") (pin "4") (pinfunction "PIN4_4") (pintype "bidirectional"))
      (node (ref "J4") (pin "6") (pinfunction "PIN6_6") (pintype "bidirectional"))
      (node (ref "J4") (pin "8") (pinfunction "PIN8_8") (pintype "bidirectional"))
      (node (ref "J6") (pin "P$10") (pinfunction "PIN9_P$10") (pintype "bidirectional"))
      (node (ref "J7") (pin "4") (pinfunction "PIN3_4") (pintype "bidirectional"))
      (node (ref "R1") (pin "P$1") (pinfunction "P$1_P$1") (pintype "passive"))
      (node (ref "R22") (pin "P$2") (pinfunction "P$2_P$2") (pintype "passive"))
      (node (ref "R23") (pin "P$2") (pinfunction "P$2_P$2") (pintype "passive"))
      (node (ref "R24") (pin "P$2") (pinfunction "P$2_P$2") (pintype "passive"))
      (node (ref "R25") (pin "P$2") (pinfunction "P$2_P$2") (pintype "passive"))
      (node (ref "R26") (pin "P$2") (pinfunction "P$2_P$2") (pintype "passive"))
      (node (ref "R27") (pin "P$2") (pinfunction "P$2_P$2") (pintype "passive"))
      (node (ref "R28") (pin "P$2") (pinfunction "P$2_P$2") (pintype "passive"))
      (node (ref "SW1") (pin "P$4") (pinfunction "P$4_P$4") (pintype "bidirectional"))
      (node (ref "SW2") (pin "P$4") (pinfunction "P$4_P$4") (pintype "bidirectional"))
      (node (ref "U1") (pin "108") (pinfunction "108_108") (pintype "bidirectional"))
      (node (ref "U1") (pin "118") (pinfunction "118_118") (pintype "bidirectional"))
      (node (ref "U1") (pin "123") (pinfunction "123_123") (pintype "bidirectional"))
      (node (ref "U1") (pin "131") (pinfunction "131_131") (pintype "bidirectional"))
      (node (ref "U1") (pin "140") (pinfunction "140_140") (pintype "bidirectional"))
      (node (ref "U1") (pin "19") (pinfunction "19_19") (pintype "bidirectional"))
      (node (ref "U1") (pin "21") (pinfunction "21_21") (pintype "bidirectional"))
      (node (ref "U1") (pin "22") (pinfunction "22_22") (pintype "bidirectional"))
      (node (ref "U1") (pin "27") (pinfunction "27_27") (pintype "bidirectional"))
      (node (ref "U1") (pin "36") (pinfunction "36_36") (pintype "bidirectional"))
      (node (ref "U1") (pin "4") (pinfunction "4_4") (pintype "bidirectional"))
      (node (ref "U1") (pin "41") (pinfunction "41_41") (pintype "bidirectional"))
      (node (ref "U1") (pin "48") (pinfunction "48_48") (pintype "bidirectional"))
      (node (ref "U1") (pin "57") (pinfunction "57_57") (pintype "bidirectional"))
      (node (ref "U1") (pin "63") (pinfunction "63_63") (pintype "bidirectional"))
      (node (ref "U1") (pin "79") (pinfunction "79_79") (pintype "bidirectional"))
      (node (ref "U1") (pin "82") (pinfunction "82_82") (pintype "bidirectional"))
      (node (ref "U1") (pin "94") (pinfunction "94_94") (pintype "bidirectional"))
      (node (ref "U1") (pin "95") (pinfunction "95_95") (pintype "bidirectional"))
      (node (ref "U1") (pin "97") (pinfunction "97_97") (pintype "bidirectional"))
      (node (ref "U1") (pin "PAD") (pinfunction "145_PAD") (pintype "bidirectional"))
      (node (ref "U2") (pin "1") (pinfunction "GND_1") (pintype "bidirectional"))
      (node (ref "U3") (pin "1") (pinfunction "GND_1") (pintype "bidirectional"))
      (node (ref "U4") (pin "1") (pinfunction "GND_1") (pintype "bidirectional"))
      (node (ref "U5") (pin "4") (pinfunction "GND_4") (pintype "bidirectional"))
      (node (ref "X1") (pin "P$2") (pinfunction "GND_P$2") (pintype "bidirectional"))
    )
    (net (code "23") (name "/LATCH") (class "Default")
      (node (ref "R17") (pin "P$1") (pinfunction "P$1_P$1") (pintype "passive"))
      (node (ref "R24") (pin "P$1") (pinfunction "P$1_P$1") (pintype "passive"))
      (node (ref "U1") (pin "142") (pinfunction "142_142") (pintype "bidirectional"))
    )
    (net (code "24") (name "/ODD0+") (class "Default")
      (node (ref "J2") (pin "P$8") (pinfunction "PIN7_P$8") (pintype "bidirectional"))
      (node (ref "U1") (pin "38") (pinfunction "38_38") (pintype "bidirectional"))
    )
    (net (code "25") (name "/ODD0-") (class "Default")
      (node (ref "J2") (pin "P$7") (pinfunction "PIN6_P$7") (pintype "bidirectional"))
      (node (ref "U1") (pin "39") (pinfunction "39_39") (pintype "bidirectional"))
    )
    (net (code "26") (name "/ODD1+") (class "Default")
      (node (ref "J2") (pin "P$10") (pinfunction "PIN9_P$10") (pintype "bidirectional"))
      (node (ref "U1") (pin "49") (pinfunction "49_49") (pintype "bidirectional"))
    )
    (net (code "27") (name "/ODD1-") (class "Default")
      (node (ref "J2") (pin "P$9") (pinfunction "PIN8_P$9") (pintype "bidirectional"))
      (node (ref "U1") (pin "50") (pinfunction "50_50") (pintype "bidirectional"))
    )
    (net (code "28") (name "/ODD2+") (class "Default")
      (node (ref "J2") (pin "P$12") (pinfunction "PIN11_P$12") (pintype "bidirectional"))
      (node (ref "U1") (pin "52") (pinfunction "52_52") (pintype "bidirectional"))
    )
    (net (code "29") (name "/ODD2-") (class "Default")
      (node (ref "J2") (pin "P$11") (pinfunction "PIN10_P$11") (pintype "bidirectional"))
      (node (ref "U1") (pin "53") (pinfunction "53_53") (pintype "bidirectional"))
    )
    (net (code "30") (name "/ODDC+") (class "Default")
      (node (ref "J2") (pin "P$16") (pinfunction "PIN15_P$16") (pintype "bidirectional"))
      (node (ref "U1") (pin "54") (pinfunction "54_54") (pintype "bidirectional"))
    )
    (net (code "31") (name "/ODDC-") (class "Default")
      (node (ref "J2") (pin "P$15") (pinfunction "PIN14_P$15") (pintype "bidirectional"))
      (node (ref "U1") (pin "55") (pinfunction "55_55") (pintype "bidirectional"))
    )
    (net (code "32") (name "/PIN_1") (class "Default")
      (node (ref "R13") (pin "P$1") (pinfunction "P$1_P$1") (pintype "passive"))
      (node (ref "U1") (pin "1") (pinfunction "1_1") (pintype "bidirectional"))
    )
    (net (code "33") (name "/PIN_2") (class "Default")
      (node (ref "R14") (pin "P$1") (pinfunction "P$1_P$1") (pintype "passive"))
      (node (ref "U1") (pin "2") (pinfunction "2_2") (pintype "bidirectional"))
    )
    (net (code "34") (name "/PIN_3") (class "Default")
      (node (ref "U1") (pin "3") (pinfunction "3_3") (pintype "bidirectional"))
    )
    (net (code "35") (name "/PIN_7") (class "Default")
      (node (ref "U1") (pin "7") (pinfunction "7_7") (pintype "bidirectional"))
    )
    (net (code "36") (name "/PIN_11") (class "Default")
      (node (ref "U1") (pin "11") (pinfunction "11_11") (pintype "bidirectional"))
    )
    (net (code "37") (name "/PIN_23") (class "Default")
      (node (ref "U1") (pin "23") (pinfunction "23_23") (pintype "bidirectional"))
    )
    (net (code "38") (name "/PIN_24") (class "Default")
      (node (ref "U1") (pin "24") (pinfunction "24_24") (pintype "bidirectional"))
    )
    (net (code "39") (name "/PIN_28") (class "Default")
      (node (ref "U1") (pin "28") (pinfunction "28_28") (pintype "bidirectional"))
    )
    (net (code "40") (name "/PIN_30") (class "Default")
      (node (ref "U1") (pin "30") (pinfunction "30_30") (pintype "bidirectional"))
    )
    (net (code "41") (name "/PIN_31") (class "Default")
      (node (ref "U1") (pin "31") (pinfunction "31_31") (pintype "bidirectional"))
    )
    (net (code "42") (name "/PIN_32") (class "Default")
      (node (ref "U1") (pin "32") (pinfunction "32_32") (pintype "bidirectional"))
    )
    (net (code "43") (name "/PIN_33") (class "Default")
      (node (ref "U1") (pin "33") (pinfunction "33_33") (pintype "bidirectional"))
    )
    (net (code "44") (name "/PIN_34") (class "Default")
      (node (ref "U1") (pin "34") (pinfunction "34_34") (pintype "bidirectional"))
    )
    (net (code "45") (name "/PIN_42") (class "Default")
      (node (ref "U1") (pin "42") (pinfunction "42_42") (pintype "bidirectional"))
    )
    (net (code "46") (name "/PIN_43") (class "Default")
      (node (ref "U1") (pin "43") (pinfunction "43_43") (pintype "bidirectional"))
    )
    (net (code "47") (name "/PIN_44") (class "Default")
      (node (ref "U1") (pin "44") (pinfunction "44_44") (pintype "bidirectional"))
    )
    (net (code "48") (name "/PIN_46") (class "Default")
      (node (ref "U1") (pin "46") (pinfunction "46_46") (pintype "bidirectional"))
    )
    (net (code "49") (name "/PIN_51") (class "Default")
      (node (ref "U1") (pin "51") (pinfunction "51_51") (pintype "bidirectional"))
    )
    (net (code "50") (name "/PIN_58") (class "Default")
      (node (ref "U1") (pin "58") (pinfunction "58_58") (pintype "bidirectional"))
    )
    (net (code "51") (name "/PIN_64") (class "Default")
      (node (ref "U1") (pin "64") (pinfunction "64_64") (pintype "bidirectional"))
    )
    (net (code "52") (name "/PIN_65") (class "Default")
      (node (ref "U1") (pin "65") (pinfunction "65_65") (pintype "bidirectional"))
    )
    (net (code "53") (name "/PIN_66") (class "Default")
      (node (ref "U1") (pin "66") (pinfunction "66_66") (pintype "bidirectional"))
    )
    (net (code "54") (name "/PIN_67") (class "Default")
      (node (ref "U1") (pin "67") (pinfunction "67_67") (pintype "bidirectional"))
    )
    (net (code "55") (name "/PIN_68") (class "Default")
      (node (ref "U1") (pin "68") (pinfunction "68_68") (pintype "bidirectional"))
    )
    (net (code "56") (name "/PIN_69") (class "Default")
      (node (ref "U1") (pin "69") (pinfunction "69_69") (pintype "bidirectional"))
    )
    (net (code "57") (name "/PIN_72") (class "Default")
      (node (ref "U1") (pin "72") (pinfunction "72_72") (pintype "bidirectional"))
    )
    (net (code "58") (name "/PIN_73") (class "Default")
      (node (ref "J5") (pin "P$1") (pinfunction "PIN0_P$1") (pintype "bidirectional"))
      (node (ref "U1") (pin "73") (pinfunction "73_73") (pintype "bidirectional"))
    )
    (net (code "59") (name "/PIN_74") (class "Default")
      (node (ref "J6") (pin "P$1") (pinfunction "PIN0_P$1") (pintype "bidirectional"))
      (node (ref "U1") (pin "74") (pinfunction "74_74") (pintype "bidirectional"))
    )
    (net (code "60") (name "/PIN_75") (class "Default")
      (node (ref "J5") (pin "P$2") (pinfunction "PIN1_P$2") (pintype "bidirectional"))
      (node (ref "U1") (pin "75") (pinfunction "75_75") (pintype "bidirectional"))
    )
    (net (code "61") (name "/PIN_76") (class "Default")
      (node (ref "J6") (pin "P$2") (pinfunction "PIN1_P$2") (pintype "bidirectional"))
      (node (ref "U1") (pin "76") (pinfunction "76_76") (pintype "bidirectional"))
    )
    (net (code "62") (name "/PIN_77") (class "Default")
      (node (ref "J5") (pin "P$3") (pinfunction "PIN2_P$3") (pintype "bidirectional"))
      (node (ref "U1") (pin "77") (pinfunction "77_77") (pintype "bidirectional"))
    )
    (net (code "63") (name "/PIN_80") (class "Default")
      (node (ref "U1") (pin "80") (pinfunction "80_80") (pintype "bidirectional"))
    )
    (net (code "64") (name "/PIN_83") (class "Default")
      (node (ref "J6") (pin "P$3") (pinfunction "PIN2_P$3") (pintype "bidirectional"))
      (node (ref "U1") (pin "83") (pinfunction "83_83") (pintype "bidirectional"))
    )
    (net (code "65") (name "/PIN_86") (class "Default")
      (node (ref "J5") (pin "P$4") (pinfunction "PIN3_P$4") (pintype "bidirectional"))
      (node (ref "U1") (pin "86") (pinfunction "86_86") (pintype "bidirectional"))
    )
    (net (code "66") (name "/PIN_87") (class "Default")
      (node (ref "J6") (pin "P$4") (pinfunction "PIN3_P$4") (pintype "bidirectional"))
      (node (ref "U1") (pin "87") (pinfunction "87_87") (pintype "bidirectional"))
    )
    (net (code "67") (name "/PIN_88") (class "Default")
      (node (ref "J5") (pin "P$5") (pinfunction "PIN4_P$5") (pintype "bidirectional"))
      (node (ref "U1") (pin "88") (pinfunction "88_88") (pintype "bidirectional"))
    )
    (net (code "68") (name "/PIN_89") (class "Default")
      (node (ref "J6") (pin "P$5") (pinfunction "PIN4_P$5") (pintype "bidirectional"))
      (node (ref "U1") (pin "89") (pinfunction "89_89") (pintype "bidirectional"))
    )
    (net (code "69") (name "/PIN_90") (class "Default")
      (node (ref "U1") (pin "90") (pinfunction "90_90") (pintype "bidirectional"))
    )
    (net (code "70") (name "/PIN_91") (class "Default")
      (node (ref "U1") (pin "91") (pinfunction "91_91") (pintype "bidirectional"))
    )
    (net (code "71") (name "/PIN_98") (class "Default")
      (node (ref "J5") (pin "P$6") (pinfunction "PIN5_P$6") (pintype "bidirectional"))
      (node (ref "U1") (pin "98") (pinfunction "98_98") (pintype "bidirectional"))
    )
    (net (code "72") (name "/PIN_99") (class "Default")
      (node (ref "J6") (pin "P$6") (pinfunction "PIN5_P$6") (pintype "bidirectional"))
      (node (ref "U1") (pin "99") (pinfunction "99_99") (pintype "bidirectional"))
    )
    (net (code "73") (name "/PIN_100") (class "Default")
      (node (ref "J5") (pin "P$7") (pinfunction "PIN6_P$7") (pintype "bidirectional"))
      (node (ref "U1") (pin "100") (pinfunction "100_100") (pintype "bidirectional"))
    )
    (net (code "74") (name "/PIN_101") (class "Default")
      (node (ref "J6") (pin "P$7") (pinfunction "PIN6_P$7") (pintype "bidirectional"))
      (node (ref "U1") (pin "101") (pinfunction "101_101") (pintype "bidirectional"))
    )
    (net (code "75") (name "/PIN_103") (class "Default")
      (node (ref "J5") (pin "P$8") (pinfunction "PIN7_P$8") (pintype "bidirectional"))
      (node (ref "U1") (pin "103") (pinfunction "103_103") (pintype "bidirectional"))
    )
    (net (code "76") (name "/PIN_104") (class "Default")
      (node (ref "J6") (pin "P$8") (pinfunction "PIN7_P$8") (pintype "bidirectional"))
      (node (ref "U1") (pin "104") (pinfunction "104_104") (pintype "bidirectional"))
    )
    (net (code "77") (name "/PIN_105") (class "Default")
      (node (ref "J5") (pin "P$9") (pinfunction "PIN8_P$9") (pintype "bidirectional"))
      (node (ref "U1") (pin "105") (pinfunction "105_105") (pintype "bidirectional"))
    )
    (net (code "78") (name "/PIN_106") (class "Default")
      (node (ref "J6") (pin "P$9") (pinfunction "PIN8_P$9") (pintype "bidirectional"))
      (node (ref "U1") (pin "106") (pinfunction "106_106") (pintype "bidirectional"))
    )
    (net (code "79") (name "/PIN_110") (class "Default")
      (node (ref "R8") (pin "P$2") (pinfunction "P$2_P$2") (pintype "passive"))
      (node (ref "SW1") (pin "P$2") (pinfunction "P$2_P$2") (pintype "bidirectional"))
      (node (ref "U1") (pin "110") (pinfunction "110_110") (pintype "bidirectional"))
    )
    (net (code "80") (name "/PIN_111") (class "Default")
      (node (ref "R12") (pin "P$2") (pinfunction "P$2_P$2") (pintype "passive"))
      (node (ref "SW2") (pin "P$2") (pinfunction "P$2_P$2") (pintype "bidirectional"))
      (node (ref "U1") (pin "111") (pinfunction "111_111") (pintype "bidirectional"))
    )
    (net (code "81") (name "/PIN_112") (class "Default")
      (node (ref "U1") (pin "112") (pinfunction "112_112") (pintype "bidirectional"))
    )
    (net (code "82") (name "/PIN_113") (class "Default")
      (node (ref "U1") (pin "113") (pinfunction "113_113") (pintype "bidirectional"))
    )
    (net (code "83") (name "/PIN_114") (class "Default")
      (node (ref "U1") (pin "114") (pinfunction "114_114") (pintype "bidirectional"))
    )
    (net (code "84") (name "/PIN_115") (class "Default")
      (node (ref "U1") (pin "115") (pinfunction "115_115") (pintype "bidirectional"))
    )
    (net (code "85") (name "/PIN_119") (class "Default")
      (node (ref "U1") (pin "119") (pinfunction "119_119") (pintype "bidirectional"))
    )
    (net (code "86") (name "/PIN_124") (class "Default")
      (node (ref "U1") (pin "124") (pinfunction "124_124") (pintype "bidirectional"))
    )
    (net (code "87") (name "/PIN_126") (class "Default")
      (node (ref "U1") (pin "126") (pinfunction "126_126") (pintype "bidirectional"))
    )
    (net (code "88") (name "/PIN_127") (class "Default")
      (node (ref "U1") (pin "127") (pinfunction "127_127") (pintype "bidirectional"))
    )
    (net (code "89") (name "/PIN_128") (class "Default")
      (node (ref "U1") (pin "128") (pinfunction "128_128") (pintype "bidirectional"))
    )
    (net (code "90") (name "/PIN_129") (class "Default")
      (node (ref "U1") (pin "129") (pinfunction "129_129") (pintype "bidirectional"))
    )
    (net (code "91") (name "/PIN_132") (class "Default")
      (node (ref "U1") (pin "132") (pinfunction "132_132") (pintype "bidirectional"))
    )
    (net (code "92") (name "/PIN_133") (class "Default")
      (node (ref "U1") (pin "133") (pinfunction "133_133") (pintype "bidirectional"))
    )
    (net (code "93") (name "/PIN_136") (class "Default")
      (node (ref "U1") (pin "136") (pinfunction "136_136") (pintype "bidirectional"))
    )
    (net (code "94") (name "/PWM{slash}EN") (class "Default")
      (node (ref "J3") (pin "P$4") (pinfunction "PIN3_P$4") (pintype "bidirectional"))
      (node (ref "U1") (pin "10") (pinfunction "10_10") (pintype "bidirectional"))
    )
    (net (code "95") (name "/REG0") (class "Default")
      (node (ref "R20") (pin "P$1") (pinfunction "P$1_P$1") (pintype "passive"))
      (node (ref "R27") (pin "P$1") (pinfunction "P$1_P$1") (pintype "passive"))
      (node (ref "U1") (pin "137") (pinfunction "137_137") (pintype "bidirectional"))
    )
    (net (code "96") (name "/REG1") (class "Default")
      (node (ref "R19") (pin "P$1") (pinfunction "P$1_P$1") (pintype "passive"))
      (node (ref "R26") (pin "P$1") (pinfunction "P$1_P$1") (pintype "passive"))
      (node (ref "U1") (pin "138") (pinfunction "138_138") (pintype "bidirectional"))
    )
    (net (code "97") (name "/REG2") (class "Default")
      (node (ref "R18") (pin "P$1") (pinfunction "P$1_P$1") (pintype "passive"))
      (node (ref "R25") (pin "P$1") (pinfunction "P$1_P$1") (pintype "passive"))
      (node (ref "U1") (pin "141") (pinfunction "141_141") (pintype "bidirectional"))
    )
    (net (code "98") (name "/RESET") (class "Default")
      (node (ref "!RESET") (pin "P$2") (pinfunction "P$2_P$2") (pintype "bidirectional"))
      (node (ref "R7") (pin "P$2") (pinfunction "P$2_P$2") (pintype "passive"))
      (node (ref "U1") (pin "125") (pinfunction "125_125") (pintype "bidirectional"))
    )
    (net (code "99") (name "/TCK") (class "Default")
      (node (ref "J1") (pin "1") (pinfunction "PIN1_1") (pintype "bidirectional"))
      (node (ref "R1") (pin "P$2") (pinfunction "P$2_P$2") (pintype "passive"))
      (node (ref "U1") (pin "16") (pinfunction "16_16") (pintype "bidirectional"))
    )
    (net (code "100") (name "/TDI") (class "Default")
      (node (ref "J1") (pin "9") (pinfunction "PIN9_9") (pintype "bidirectional"))
      (node (ref "R3") (pin "P$1") (pinfunction "P$1_P$1") (pintype "passive"))
      (node (ref "U1") (pin "15") (pinfunction "15_15") (pintype "bidirectional"))
    )
    (net (code "101") (name "/TDO") (class "Default")
      (node (ref "J1") (pin "3") (pinfunction "PIN3_3") (pintype "bidirectional"))
      (node (ref "U1") (pin "20") (pinfunction "20_20") (pintype "bidirectional"))
    )
    (net (code "102") (name "/TMS") (class "Default")
      (node (ref "J1") (pin "5") (pinfunction "PIN5_5") (pintype "bidirectional"))
      (node (ref "R2") (pin "P$1") (pinfunction "P$1_P$1") (pintype "passive"))
      (node (ref "U1") (pin "18") (pinfunction "18_18") (pintype "bidirectional"))
    )
    (net (code "103") (name "/~{CONFIG}") (class "Default")
      (node (ref "!CONFIG") (pin "P$2") (pinfunction "P$2_P$2") (pintype "bidirectional"))
      (node (ref "R5") (pin "P$2") (pinfunction "P$2_P$2") (pintype "passive"))
      (node (ref "U1") (pin "14") (pinfunction "14_14") (pintype "bidirectional"))
    )
    (net (code "104") (name "/~{CSO}") (class "Default")
      (node (ref "R11") (pin "P$2") (pinfunction "P$2_P$2") (pintype "passive"))
      (node (ref "U1") (pin "8") (pinfunction "8_8") (pintype "bidirectional"))
      (node (ref "U5") (pin "1") (pinfunction "~{S}_1") (pintype "bidirectional"))
    )
    (net (code "105") (name "/~{STATUS}") (class "Default")
      (node (ref "R4") (pin "P$2") (pinfunction "P$2_P$2") (pintype "passive"))
      (node (ref "U1") (pin "9") (pinfunction "9_9") (pintype "bidirectional"))
    )
    (net (code "106") (name "Net-(D1-PadANODE)") (class "Default")
      (node (ref "D1") (pin "ANODE") (pinfunction "ANODE_ANODE") (pintype "power_in"))
      (node (ref "R13") (pin "P$2") (pinfunction "P$2_P$2") (pintype "passive"))
    )
    (net (code "107") (name "Net-(D2-PadANODE)") (class "Default")
      (node (ref "D2") (pin "ANODE") (pinfunction "ANODE_ANODE") (pintype "power_in"))
      (node (ref "R14") (pin "P$2") (pinfunction "P$2_P$2") (pintype "passive"))
    )
    (net (code "108") (name "Net-(J4-PIN1)") (class "Default")
      (node (ref "J4") (pin "1") (pinfunction "PIN1_1") (pintype "bidirectional"))
      (node (ref "R15") (pin "P$2") (pinfunction "P$2_P$2") (pintype "passive"))
    )
    (net (code "109") (name "Net-(J4-PIN3)") (class "Default")
      (node (ref "J4") (pin "3") (pinfunction "PIN3_3") (pintype "bidirectional"))
      (node (ref "R16") (pin "P$2") (pinfunction "P$2_P$2") (pintype "passive"))
    )
    (net (code "110") (name "Net-(J4-PIN5)") (class "Default")
      (node (ref "J4") (pin "5") (pinfunction "PIN5_5") (pintype "bidirectional"))
      (node (ref "R17") (pin "P$2") (pinfunction "P$2_P$2") (pintype "passive"))
    )
    (net (code "111") (name "Net-(J4-PIN7)") (class "Default")
      (node (ref "J4") (pin "7") (pinfunction "PIN7_7") (pintype "bidirectional"))
      (node (ref "R18") (pin "P$2") (pinfunction "P$2_P$2") (pintype "passive"))
    )
    (net (code "112") (name "Net-(J4-PIN9)") (class "Default")
      (node (ref "J4") (pin "9") (pinfunction "PIN9_9") (pintype "bidirectional"))
      (node (ref "R19") (pin "P$2") (pinfunction "P$2_P$2") (pintype "passive"))
    )
    (net (code "113") (name "Net-(J4-PIN11)") (class "Default")
      (node (ref "J4") (pin "11") (pinfunction "PIN11_11") (pintype "bidirectional"))
      (node (ref "R20") (pin "P$2") (pinfunction "P$2_P$2") (pintype "passive"))
    )
    (net (code "114") (name "Net-(J4-PIN13)") (class "Default")
      (node (ref "J4") (pin "13") (pinfunction "PIN13_13") (pintype "bidirectional"))
      (node (ref "R21") (pin "P$2") (pinfunction "P$2_P$2") (pintype "passive"))
    )
    (net (code "115") (name "unconnected-(!CONFIG-PadP$1)") (class "Default")
      (node (ref "!CONFIG") (pin "P$1") (pinfunction "P$1_P$1") (pintype "bidirectional"))
    )
    (net (code "116") (name "unconnected-(!CONFIG-PadP$3)") (class "Default")
      (node (ref "!CONFIG") (pin "P$3") (pinfunction "P$3_P$3") (pintype "bidirectional"))
    )
    (net (code "117") (name "unconnected-(!RESET-PadP$1)") (class "Default")
      (node (ref "!RESET") (pin "P$1") (pinfunction "P$1_P$1") (pintype "bidirectional"))
    )
    (net (code "118") (name "unconnected-(!RESET-PadP$3)") (class "Default")
      (node (ref "!RESET") (pin "P$3") (pinfunction "P$3_P$3") (pintype "bidirectional"))
    )
    (net (code "119") (name "unconnected-(J1-PIN6-Pad6)") (class "Default")
      (node (ref "J1") (pin "6") (pinfunction "PIN6_6") (pintype "bidirectional"))
    )
    (net (code "120") (name "unconnected-(J1-PIN7-Pad7)") (class "Default")
      (node (ref "J1") (pin "7") (pinfunction "PIN7_7") (pintype "bidirectional"))
    )
    (net (code "121") (name "unconnected-(J1-PIN8-Pad8)") (class "Default")
      (node (ref "J1") (pin "8") (pinfunction "PIN8_8") (pintype "bidirectional"))
    )
    (net (code "122") (name "unconnected-(J2-PIN3-PadP$4)") (class "Default")
      (node (ref "J2") (pin "P$4") (pinfunction "PIN3_P$4") (pintype "bidirectional"))
    )
    (net (code "123") (name "unconnected-(J2-PIN16-PadP$17)") (class "Default")
      (node (ref "J2") (pin "P$17") (pinfunction "PIN16_P$17") (pintype "bidirectional"))
    )
    (net (code "124") (name "unconnected-(J2-PIN17-PadP$18)") (class "Default")
      (node (ref "J2") (pin "P$18") (pinfunction "PIN17_P$18") (pintype "bidirectional"))
    )
    (net (code "125") (name "unconnected-(J2-PIN28-PadP$29)") (class "Default")
      (node (ref "J2") (pin "P$29") (pinfunction "PIN28_P$29") (pintype "bidirectional"))
    )
    (net (code "126") (name "unconnected-(J2-PIN29-PadP$30)") (class "Default")
      (node (ref "J2") (pin "P$30") (pinfunction "PIN29_P$30") (pintype "bidirectional"))
    )
    (net (code "127") (name "unconnected-(J3-PIN2-PadP$3)") (class "Default")
      (node (ref "J3") (pin "P$3") (pinfunction "PIN2_P$3") (pintype "bidirectional"))
    )
    (net (code "128") (name "unconnected-(SW1-PadP$1)") (class "Default")
      (node (ref "SW1") (pin "P$1") (pinfunction "P$1_P$1") (pintype "bidirectional"))
    )
    (net (code "129") (name "unconnected-(SW1-PadP$3)") (class "Default")
      (node (ref "SW1") (pin "P$3") (pinfunction "P$3_P$3") (pintype "bidirectional"))
    )
    (net (code "130") (name "unconnected-(SW2-PadP$1)") (class "Default")
      (node (ref "SW2") (pin "P$1") (pinfunction "P$1_P$1") (pintype "bidirectional"))
    )
    (net (code "131") (name "unconnected-(SW2-PadP$3)") (class "Default")
      (node (ref "SW2") (pin "P$3") (pinfunction "P$3_P$3") (pintype "bidirectional"))
    )
    (net (code "132") (name "unconnected-(X1-STBY-PadP$1)") (class "Default")
      (node (ref "X1") (pin "P$1") (pinfunction "STBY_P$1") (pintype "bidirectional"))
    )
  )
)
